# Astable_555_Timer.net
KiCad netlist of a schematic drawn in EAGLE
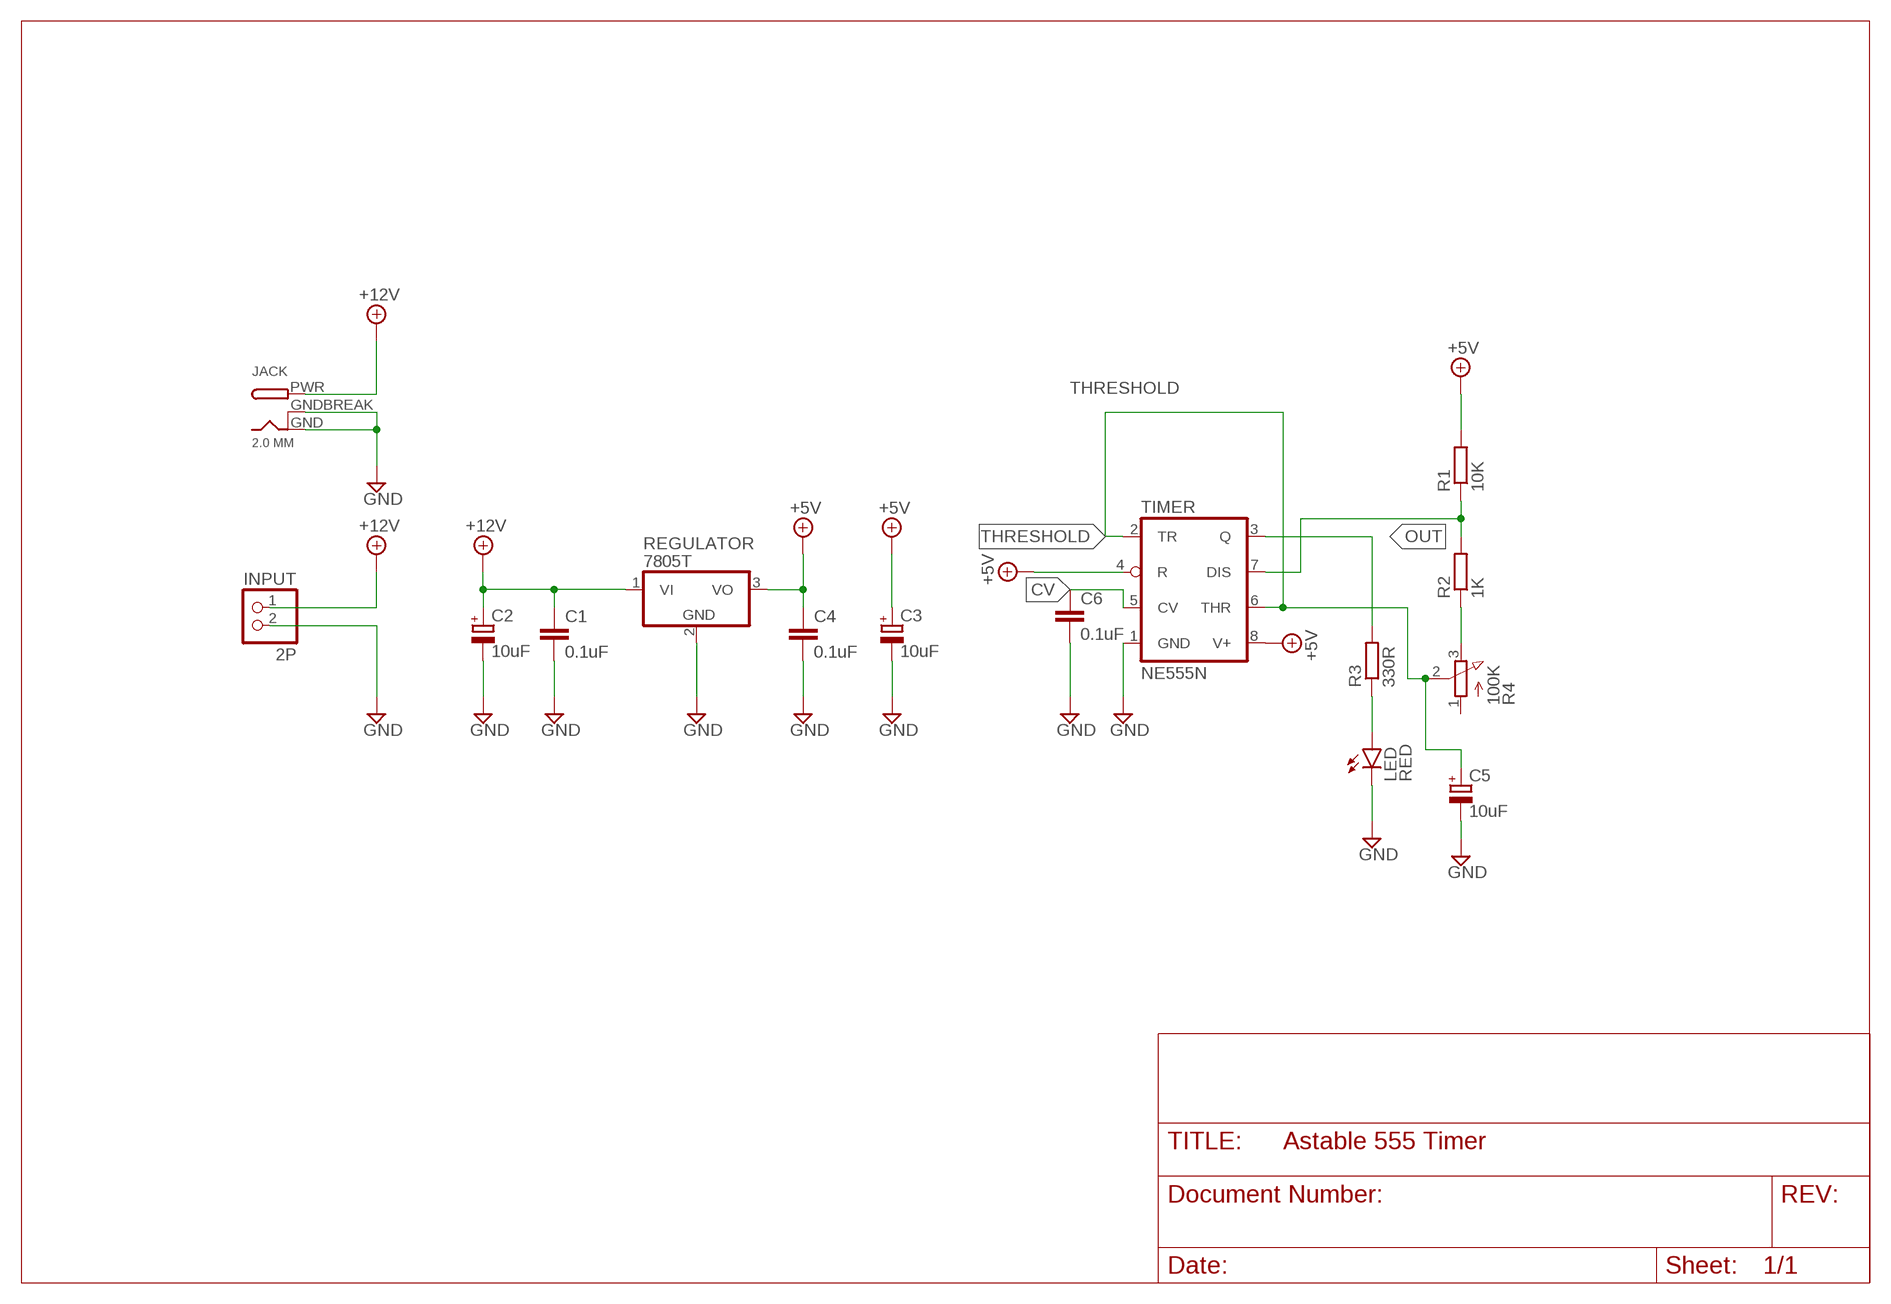
[diagram p0: schematic, sheet 1]

(export (version "E")
  (design (tool "Eeschema 10.0.6"))
  (components
    (comp (ref "C1")
      (value "0.1uF")
      (footprint "eagle-import:C050-030X075")
      (libsource (lib "eagle-import") (part "C-EU050-030X075"))
    )
    (comp (ref "C2")
      (value "10uF")
      (footprint "eagle-import:E3,5-8")
      (libsource (lib "eagle-import") (part "CPOL-EUE3.5-8"))
    )
    (comp (ref "C3")
      (value "10uF")
      (footprint "eagle-import:E3,5-8")
      (libsource (lib "eagle-import") (part "CPOL-EUE3.5-8"))
    )
    (comp (ref "C4")
      (value "0.1uF")
      (footprint "eagle-import:C050-030X075")
      (libsource (lib "eagle-import") (part "C-EU050-030X075"))
    )
    (comp (ref "C5")
      (value "10uF")
      (footprint "eagle-import:E3,5-8")
      (libsource (lib "eagle-import") (part "CPOL-EUE3.5-8"))
    )
    (comp (ref "C6")
      (value "0.1uF")
      (footprint "eagle-import:C050-030X075")
      (libsource (lib "eagle-import") (part "C-EU050-030X075"))
    )
    (comp (ref "INPUT")
      (value "2P")
      (footprint "eagle-import:1X02")
      (libsource (lib "eagle-import") (part "PINHD-1X2"))
    )
    (comp (ref "JACK")
      (value "2.0 MM")
      (footprint "eagle-import:DCJACK_2MM_PTH")
      (libsource (lib "eagle-import") (part "DCBARRELPTH"))
    )
    (comp (ref "LED")
      (value "RED")
      (footprint "eagle-import:LED5MM")
      (libsource (lib "eagle-import") (part "LED5MM"))
    )
    (comp (ref "R1")
      (value "10K")
      (footprint "eagle-import:0207_10")
      (libsource (lib "eagle-import") (part "R-EU_0207/10"))
    )
    (comp (ref "R2")
      (value "1K")
      (footprint "eagle-import:0207_10")
      (libsource (lib "eagle-import") (part "R-EU_0207/10"))
    )
    (comp (ref "R3")
      (value "330R")
      (footprint "eagle-import:0207_10")
      (libsource (lib "eagle-import") (part "R-EU_0207/10"))
    )
    (comp (ref "R4")
      (value "100K")
      (footprint "eagle-import:3RP_1610N")
      (libsource (lib "eagle-import") (part "3RP/1610N"))
    )
    (comp (ref "REGULATOR")
      (value "7805T")
      (footprint "eagle-import:TO220H")
      (libsource (lib "eagle-import") (part "78T05"))
    )
    (comp (ref "TIMER")
      (value "NE555N")
      (footprint "eagle-import:DIL08")
      (libsource (lib "eagle-import") (part "555NNE"))
    )
  )
  (nets
    (net (code "1") (name "+5V") (class "Default")
      (node (ref "C3") (pin "+") (pinfunction "+_+") (pintype "passive"))
      (node (ref "C4") (pin "1") (pinfunction "1_1") (pintype "passive"))
      (node (ref "R1") (pin "2") (pinfunction "2_2") (pintype "passive"))
      (node (ref "REGULATOR") (pin "3") (pinfunction "VO_3") (pintype "passive"))
      (node (ref "TIMER") (pin "4") (pinfunction "R_4") (pintype "input"))
      (node (ref "TIMER") (pin "8") (pinfunction "V+_8") (pintype "power_in"))
    )
    (net (code "2") (name "+12V") (class "Default")
      (node (ref "C1") (pin "1") (pinfunction "1_1") (pintype "passive"))
      (node (ref "C2") (pin "+") (pinfunction "+_+") (pintype "passive"))
      (node (ref "INPUT") (pin "1") (pinfunction "1_1") (pintype "passive"))
      (node (ref "JACK") (pin "PWR") (pinfunction "PWR_PWR") (pintype "power_in"))
      (node (ref "REGULATOR") (pin "1") (pinfunction "VI_1") (pintype "input"))
    )
    (net (code "3") (name "CV") (class "Default")
      (node (ref "C6") (pin "1") (pinfunction "1_1") (pintype "passive"))
      (node (ref "TIMER") (pin "5") (pinfunction "CV_5") (pintype "input"))
    )
    (net (code "4") (name "GND") (class "Default")
      (node (ref "C1") (pin "2") (pinfunction "2_2") (pintype "passive"))
      (node (ref "C2") (pin "-") (pinfunction "-_-") (pintype "passive"))
      (node (ref "C3") (pin "-") (pinfunction "-_-") (pintype "passive"))
      (node (ref "C4") (pin "2") (pinfunction "2_2") (pintype "passive"))
      (node (ref "C5") (pin "-") (pinfunction "-_-") (pintype "passive"))
      (node (ref "C6") (pin "2") (pinfunction "2_2") (pintype "passive"))
      (node (ref "INPUT") (pin "2") (pinfunction "2_2") (pintype "passive"))
      (node (ref "JACK") (pin "GND") (pinfunction "GND_GND") (pintype "power_in"))
      (node (ref "JACK") (pin "GNDBREAK") (pinfunction "GNDBREAK_GNDBREAK") (pintype "power_in"))
      (node (ref "LED") (pin "K") (pinfunction "C_K") (pintype "passive"))
      (node (ref "REGULATOR") (pin "2") (pinfunction "GND_2") (pintype "passive"))
      (node (ref "TIMER") (pin "1") (pinfunction "GND_1") (pintype "power_in"))
    )
    (net (code "5") (name "Net-(LED-PadA)") (class "Default")
      (node (ref "LED") (pin "A") (pinfunction "A_A") (pintype "passive"))
      (node (ref "R3") (pin "1") (pinfunction "1_1") (pintype "passive"))
    )
    (net (code "6") (name "Net-(R4-E)") (class "Default")
      (node (ref "R2") (pin "1") (pinfunction "1_1") (pintype "passive"))
      (node (ref "R4") (pin "3") (pinfunction "E_3") (pintype "passive"))
    )
    (net (code "7") (name "Net-(TIMER-DIS)") (class "Default")
      (node (ref "R1") (pin "1") (pinfunction "1_1") (pintype "passive"))
      (node (ref "R2") (pin "2") (pinfunction "2_2") (pintype "passive"))
      (node (ref "TIMER") (pin "7") (pinfunction "DIS_7") (pintype "input"))
    )
    (net (code "8") (name "OUT") (class "Default")
      (node (ref "R3") (pin "2") (pinfunction "2_2") (pintype "passive"))
      (node (ref "TIMER") (pin "3") (pinfunction "Q_3") (pintype "output"))
    )
    (net (code "9") (name "THRESHOLD") (class "Default")
      (node (ref "C5") (pin "+") (pinfunction "+_+") (pintype "passive"))
      (node (ref "R4") (pin "2") (pinfunction "S_2") (pintype "passive"))
      (node (ref "TIMER") (pin "2") (pinfunction "TR_2") (pintype "input"))
      (node (ref "TIMER") (pin "6") (pinfunction "THR_6") (pintype "input"))
    )
    (net (code "10") (name "unconnected-(R4-A-Pad1)") (class "Default")
      (node (ref "R4") (pin "1") (pinfunction "A_1") (pintype "passive"))
    )
  )
)
